# 8565_adapter.net
KiCad netlist of a schematic drawn in EAGLE
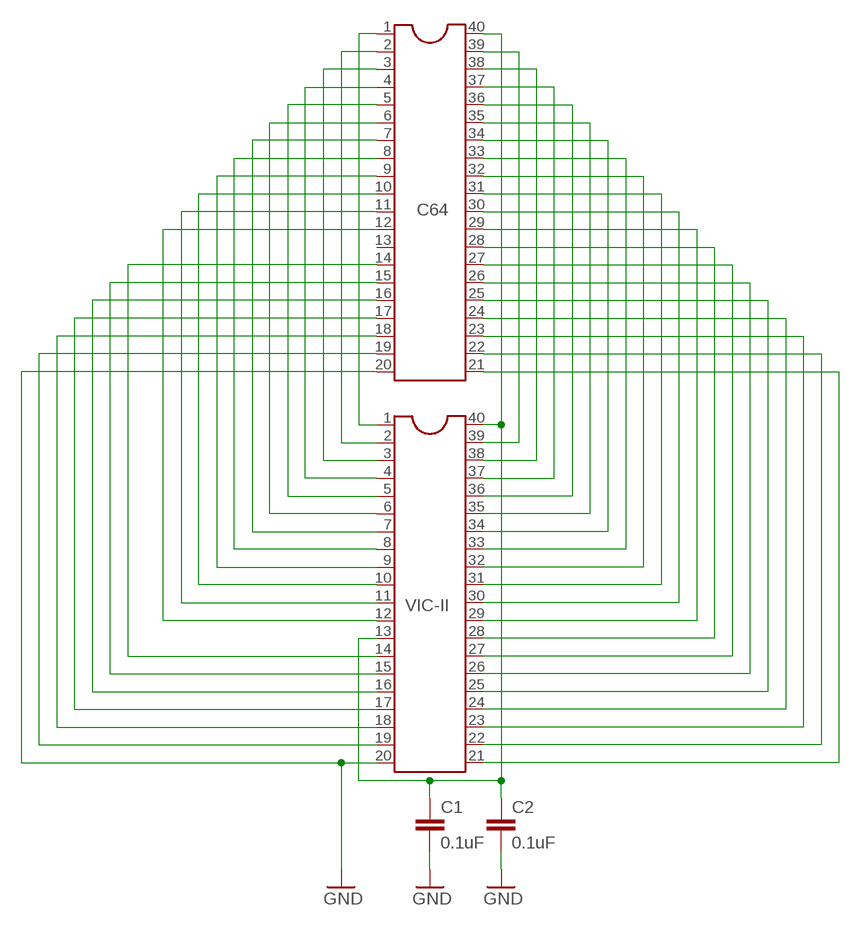
[diagram p0: schematic, sheet 1]

(export (version "E")
  (design (tool "Eeschema 10.0.6"))
  (components
    (comp (ref "C1")
      (value "0.1uF")
      (footprint "eagle-import:0603-CAP")
      (libsource (lib "eagle-import") (part "CAP0603-CAP"))
    )
    (comp (ref "C2")
      (value "0.1uF")
      (footprint "eagle-import:CAP-PTH-SMALLEZ")
      (libsource (lib "eagle-import") (part "CAPEZ"))
    )
    (comp (ref "C64")
      (value "DIL40NO_SILK")
      (footprint "eagle-import:DIL40-TINY")
      (libsource (lib "eagle-import") (part "DIL40NO_SILK"))
    )
    (comp (ref "VIC-II")
      (value "DIL40")
      (footprint "eagle-import:DIL40")
      (libsource (lib "eagle-import") (part "DIL40"))
    )
  )
  (nets
    (net (code "1") (name "GND") (class "Default")
      (node (ref "C1") (pin "2") (pinfunction "2_2") (pintype "passive"))
      (node (ref "C2") (pin "2") (pinfunction "2_2") (pintype "passive"))
      (node (ref "C64") (pin "20") (pinfunction "20_20") (pintype "passive"))
      (node (ref "VIC-II") (pin "20") (pinfunction "20_20") (pintype "passive"))
    )
    (net (code "2") (name "Net-(C1-Pad1)") (class "Default")
      (node (ref "C1") (pin "1") (pinfunction "1_1") (pintype "passive"))
      (node (ref "C2") (pin "1") (pinfunction "1_1") (pintype "passive"))
      (node (ref "C64") (pin "40") (pinfunction "40_40") (pintype "passive"))
      (node (ref "VIC-II") (pin "13") (pinfunction "13_13") (pintype "passive"))
      (node (ref "VIC-II") (pin "40") (pinfunction "40_40") (pintype "passive"))
    )
    (net (code "3") (name "Net-(C64-Pad1)") (class "Default")
      (node (ref "C64") (pin "1") (pinfunction "1_1") (pintype "passive"))
      (node (ref "VIC-II") (pin "1") (pinfunction "1_1") (pintype "passive"))
    )
    (net (code "4") (name "Net-(C64-Pad2)") (class "Default")
      (node (ref "C64") (pin "2") (pinfunction "2_2") (pintype "passive"))
      (node (ref "VIC-II") (pin "2") (pinfunction "2_2") (pintype "passive"))
    )
    (net (code "5") (name "Net-(C64-Pad3)") (class "Default")
      (node (ref "C64") (pin "3") (pinfunction "3_3") (pintype "passive"))
      (node (ref "VIC-II") (pin "3") (pinfunction "3_3") (pintype "passive"))
    )
    (net (code "6") (name "Net-(C64-Pad4)") (class "Default")
      (node (ref "C64") (pin "4") (pinfunction "4_4") (pintype "passive"))
      (node (ref "VIC-II") (pin "4") (pinfunction "4_4") (pintype "passive"))
    )
    (net (code "7") (name "Net-(C64-Pad5)") (class "Default")
      (node (ref "C64") (pin "5") (pinfunction "5_5") (pintype "passive"))
      (node (ref "VIC-II") (pin "5") (pinfunction "5_5") (pintype "passive"))
    )
    (net (code "8") (name "Net-(C64-Pad6)") (class "Default")
      (node (ref "C64") (pin "6") (pinfunction "6_6") (pintype "passive"))
      (node (ref "VIC-II") (pin "6") (pinfunction "6_6") (pintype "passive"))
    )
    (net (code "9") (name "Net-(C64-Pad7)") (class "Default")
      (node (ref "C64") (pin "7") (pinfunction "7_7") (pintype "passive"))
      (node (ref "VIC-II") (pin "7") (pinfunction "7_7") (pintype "passive"))
    )
    (net (code "10") (name "Net-(C64-Pad8)") (class "Default")
      (node (ref "C64") (pin "8") (pinfunction "8_8") (pintype "passive"))
      (node (ref "VIC-II") (pin "8") (pinfunction "8_8") (pintype "passive"))
    )
    (net (code "11") (name "Net-(C64-Pad9)") (class "Default")
      (node (ref "C64") (pin "9") (pinfunction "9_9") (pintype "passive"))
      (node (ref "VIC-II") (pin "9") (pinfunction "9_9") (pintype "passive"))
    )
    (net (code "12") (name "Net-(C64-Pad10)") (class "Default")
      (node (ref "C64") (pin "10") (pinfunction "10_10") (pintype "passive"))
      (node (ref "VIC-II") (pin "10") (pinfunction "10_10") (pintype "passive"))
    )
    (net (code "13") (name "Net-(C64-Pad11)") (class "Default")
      (node (ref "C64") (pin "11") (pinfunction "11_11") (pintype "passive"))
      (node (ref "VIC-II") (pin "11") (pinfunction "11_11") (pintype "passive"))
    )
    (net (code "14") (name "Net-(C64-Pad12)") (class "Default")
      (node (ref "C64") (pin "12") (pinfunction "12_12") (pintype "passive"))
      (node (ref "VIC-II") (pin "12") (pinfunction "12_12") (pintype "passive"))
    )
    (net (code "15") (name "Net-(C64-Pad14)") (class "Default")
      (node (ref "C64") (pin "14") (pinfunction "14_14") (pintype "passive"))
      (node (ref "VIC-II") (pin "14") (pinfunction "14_14") (pintype "passive"))
    )
    (net (code "16") (name "Net-(C64-Pad15)") (class "Default")
      (node (ref "C64") (pin "15") (pinfunction "15_15") (pintype "passive"))
      (node (ref "VIC-II") (pin "15") (pinfunction "15_15") (pintype "passive"))
    )
    (net (code "17") (name "Net-(C64-Pad16)") (class "Default")
      (node (ref "C64") (pin "16") (pinfunction "16_16") (pintype "passive"))
      (node (ref "VIC-II") (pin "16") (pinfunction "16_16") (pintype "passive"))
    )
    (net (code "18") (name "Net-(C64-Pad17)") (class "Default")
      (node (ref "C64") (pin "17") (pinfunction "17_17") (pintype "passive"))
      (node (ref "VIC-II") (pin "17") (pinfunction "17_17") (pintype "passive"))
    )
    (net (code "19") (name "Net-(C64-Pad18)") (class "Default")
      (node (ref "C64") (pin "18") (pinfunction "18_18") (pintype "passive"))
      (node (ref "VIC-II") (pin "18") (pinfunction "18_18") (pintype "passive"))
    )
    (net (code "20") (name "Net-(C64-Pad19)") (class "Default")
      (node (ref "C64") (pin "19") (pinfunction "19_19") (pintype "passive"))
      (node (ref "VIC-II") (pin "19") (pinfunction "19_19") (pintype "passive"))
    )
    (net (code "21") (name "Net-(C64-Pad21)") (class "Default")
      (node (ref "C64") (pin "21") (pinfunction "21_21") (pintype "passive"))
      (node (ref "VIC-II") (pin "21") (pinfunction "21_21") (pintype "passive"))
    )
    (net (code "22") (name "Net-(C64-Pad22)") (class "Default")
      (node (ref "C64") (pin "22") (pinfunction "22_22") (pintype "passive"))
      (node (ref "VIC-II") (pin "22") (pinfunction "22_22") (pintype "passive"))
    )
    (net (code "23") (name "Net-(C64-Pad23)") (class "Default")
      (node (ref "C64") (pin "23") (pinfunction "23_23") (pintype "passive"))
      (node (ref "VIC-II") (pin "23") (pinfunction "23_23") (pintype "passive"))
    )
    (net (code "24") (name "Net-(C64-Pad24)") (class "Default")
      (node (ref "C64") (pin "24") (pinfunction "24_24") (pintype "passive"))
      (node (ref "VIC-II") (pin "24") (pinfunction "24_24") (pintype "passive"))
    )
    (net (code "25") (name "Net-(C64-Pad25)") (class "Default")
      (node (ref "C64") (pin "25") (pinfunction "25_25") (pintype "passive"))
      (node (ref "VIC-II") (pin "25") (pinfunction "25_25") (pintype "passive"))
    )
    (net (code "26") (name "Net-(C64-Pad26)") (class "Default")
      (node (ref "C64") (pin "26") (pinfunction "26_26") (pintype "passive"))
      (node (ref "VIC-II") (pin "26") (pinfunction "26_26") (pintype "passive"))
    )
    (net (code "27") (name "Net-(C64-Pad27)") (class "Default")
      (node (ref "C64") (pin "27") (pinfunction "27_27") (pintype "passive"))
      (node (ref "VIC-II") (pin "27") (pinfunction "27_27") (pintype "passive"))
    )
    (net (code "28") (name "Net-(C64-Pad28)") (class "Default")
      (node (ref "C64") (pin "28") (pinfunction "28_28") (pintype "passive"))
      (node (ref "VIC-II") (pin "28") (pinfunction "28_28") (pintype "passive"))
    )
    (net (code "29") (name "Net-(C64-Pad29)") (class "Default")
      (node (ref "C64") (pin "29") (pinfunction "29_29") (pintype "passive"))
      (node (ref "VIC-II") (pin "29") (pinfunction "29_29") (pintype "passive"))
    )
    (net (code "30") (name "Net-(C64-Pad30)") (class "Default")
      (node (ref "C64") (pin "30") (pinfunction "30_30") (pintype "passive"))
      (node (ref "VIC-II") (pin "30") (pinfunction "30_30") (pintype "passive"))
    )
    (net (code "31") (name "Net-(C64-Pad31)") (class "Default")
      (node (ref "C64") (pin "31") (pinfunction "31_31") (pintype "passive"))
      (node (ref "VIC-II") (pin "31") (pinfunction "31_31") (pintype "passive"))
    )
    (net (code "32") (name "Net-(C64-Pad32)") (class "Default")
      (node (ref "C64") (pin "32") (pinfunction "32_32") (pintype "passive"))
      (node (ref "VIC-II") (pin "32") (pinfunction "32_32") (pintype "passive"))
    )
    (net (code "33") (name "Net-(C64-Pad33)") (class "Default")
      (node (ref "C64") (pin "33") (pinfunction "33_33") (pintype "passive"))
      (node (ref "VIC-II") (pin "33") (pinfunction "33_33") (pintype "passive"))
    )
    (net (code "34") (name "Net-(C64-Pad34)") (class "Default")
      (node (ref "C64") (pin "34") (pinfunction "34_34") (pintype "passive"))
      (node (ref "VIC-II") (pin "34") (pinfunction "34_34") (pintype "passive"))
    )
    (net (code "35") (name "Net-(C64-Pad35)") (class "Default")
      (node (ref "C64") (pin "35") (pinfunction "35_35") (pintype "passive"))
      (node (ref "VIC-II") (pin "35") (pinfunction "35_35") (pintype "passive"))
    )
    (net (code "36") (name "Net-(C64-Pad36)") (class "Default")
      (node (ref "C64") (pin "36") (pinfunction "36_36") (pintype "passive"))
      (node (ref "VIC-II") (pin "36") (pinfunction "36_36") (pintype "passive"))
    )
    (net (code "37") (name "Net-(C64-Pad37)") (class "Default")
      (node (ref "C64") (pin "37") (pinfunction "37_37") (pintype "passive"))
      (node (ref "VIC-II") (pin "37") (pinfunction "37_37") (pintype "passive"))
    )
    (net (code "38") (name "Net-(C64-Pad38)") (class "Default")
      (node (ref "C64") (pin "38") (pinfunction "38_38") (pintype "passive"))
      (node (ref "VIC-II") (pin "38") (pinfunction "38_38") (pintype "passive"))
    )
    (net (code "39") (name "Net-(C64-Pad39)") (class "Default")
      (node (ref "C64") (pin "39") (pinfunction "39_39") (pintype "passive"))
      (node (ref "VIC-II") (pin "39") (pinfunction "39_39") (pintype "passive"))
    )
    (net (code "40") (name "unconnected-(C64-Pad13)") (class "Default")
      (node (ref "C64") (pin "13") (pinfunction "13_13") (pintype "passive"))
    )
  )
)
